# 6-way-pot-scanner-module.net
KiCad netlist of a schematic drawn in EAGLE
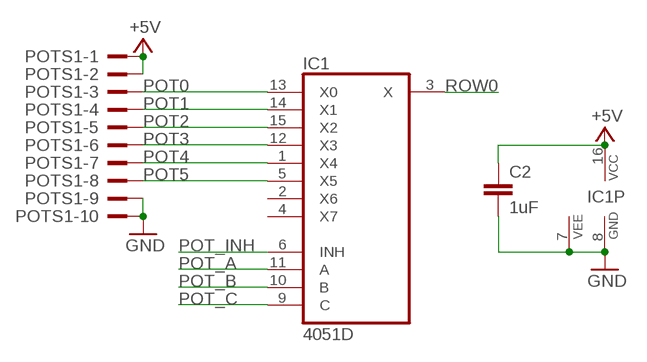
[diagram p0: schematic, sheet 1]

(export (version "E")
  (design (tool "Eeschema 10.0.6"))
  (components
    (comp (ref "C2")
      (value "1uF")
      (footprint "eagle-import:C0603-J")
      (libsource (lib "eagle-import") (part "C-EU-J0603"))
    )
    (comp (ref "IC1")
      (value "4051D")
      (footprint "eagle-import:SO16")
      (libsource (lib "eagle-import") (part "4051D"))
    )
    (comp (ref "POTS1")
      (value "CONN-IDC-10PS")
      (footprint "eagle-import:CONN-IDC10P-S")
      (libsource (lib "eagle-import") (part "CONN-IDC-10PS"))
    )
  )
  (nets
    (net (code "1") (name "+5V") (class "Default")
      (node (ref "C2") (pin "1") (pinfunction "1_1") (pintype "passive"))
      (node (ref "IC1") (pin "16") (pinfunction "VCC_16") (pintype "power_in"))
      (node (ref "POTS1") (pin "1") (pinfunction "KL_1") (pintype "passive"))
      (node (ref "POTS1") (pin "2") (pinfunction "KL_2") (pintype "passive"))
    )
    (net (code "2") (name "/POT0") (class "Default")
      (node (ref "IC1") (pin "13") (pinfunction "X0_13") (pintype "bidirectional"))
      (node (ref "POTS1") (pin "3") (pinfunction "KL_3") (pintype "passive"))
    )
    (net (code "3") (name "/POT1") (class "Default")
      (node (ref "IC1") (pin "14") (pinfunction "X1_14") (pintype "bidirectional"))
      (node (ref "POTS1") (pin "4") (pinfunction "KL_4") (pintype "passive"))
    )
    (net (code "4") (name "/POT2") (class "Default")
      (node (ref "IC1") (pin "15") (pinfunction "X2_15") (pintype "bidirectional"))
      (node (ref "POTS1") (pin "5") (pinfunction "KL_5") (pintype "passive"))
    )
    (net (code "5") (name "/POT3") (class "Default")
      (node (ref "IC1") (pin "12") (pinfunction "X3_12") (pintype "bidirectional"))
      (node (ref "POTS1") (pin "6") (pinfunction "KL_6") (pintype "passive"))
    )
    (net (code "6") (name "/POT4") (class "Default")
      (node (ref "IC1") (pin "1") (pinfunction "X4_1") (pintype "bidirectional"))
      (node (ref "POTS1") (pin "7") (pinfunction "KL_7") (pintype "passive"))
    )
    (net (code "7") (name "/POT5") (class "Default")
      (node (ref "IC1") (pin "5") (pinfunction "X5_5") (pintype "bidirectional"))
      (node (ref "POTS1") (pin "8") (pinfunction "KL_8") (pintype "passive"))
    )
    (net (code "8") (name "/POT_A") (class "Default")
      (node (ref "IC1") (pin "11") (pinfunction "A_11") (pintype "input"))
    )
    (net (code "9") (name "/POT_B") (class "Default")
      (node (ref "IC1") (pin "10") (pinfunction "B_10") (pintype "input"))
    )
    (net (code "10") (name "/POT_C") (class "Default")
      (node (ref "IC1") (pin "9") (pinfunction "C_9") (pintype "input"))
    )
    (net (code "11") (name "/POT_INH") (class "Default")
      (node (ref "IC1") (pin "6") (pinfunction "INH_6") (pintype "input"))
    )
    (net (code "12") (name "/ROW0") (class "Default")
      (node (ref "IC1") (pin "3") (pinfunction "X_3") (pintype "bidirectional"))
    )
    (net (code "13") (name "GND") (class "Default")
      (node (ref "C2") (pin "2") (pinfunction "2_2") (pintype "passive"))
      (node (ref "IC1") (pin "7") (pinfunction "VEE_7") (pintype "power_in"))
      (node (ref "IC1") (pin "8") (pinfunction "GND_8") (pintype "power_in"))
      (node (ref "POTS1") (pin "10") (pinfunction "KL_10") (pintype "passive"))
      (node (ref "POTS1") (pin "9") (pinfunction "KL_9") (pintype "passive"))
    )
    (net (code "14") (name "unconnected-(IC1A-X6-Pad2)") (class "Default")
      (node (ref "IC1") (pin "2") (pinfunction "X6_2") (pintype "bidirectional"))
    )
    (net (code "15") (name "unconnected-(IC1A-X7-Pad4)") (class "Default")
      (node (ref "IC1") (pin "4") (pinfunction "X7_4") (pintype "bidirectional"))
    )
  )
)
